# 5VV10_AND_BUCK.net
KiCad netlist of a schematic drawn in Altium Designer
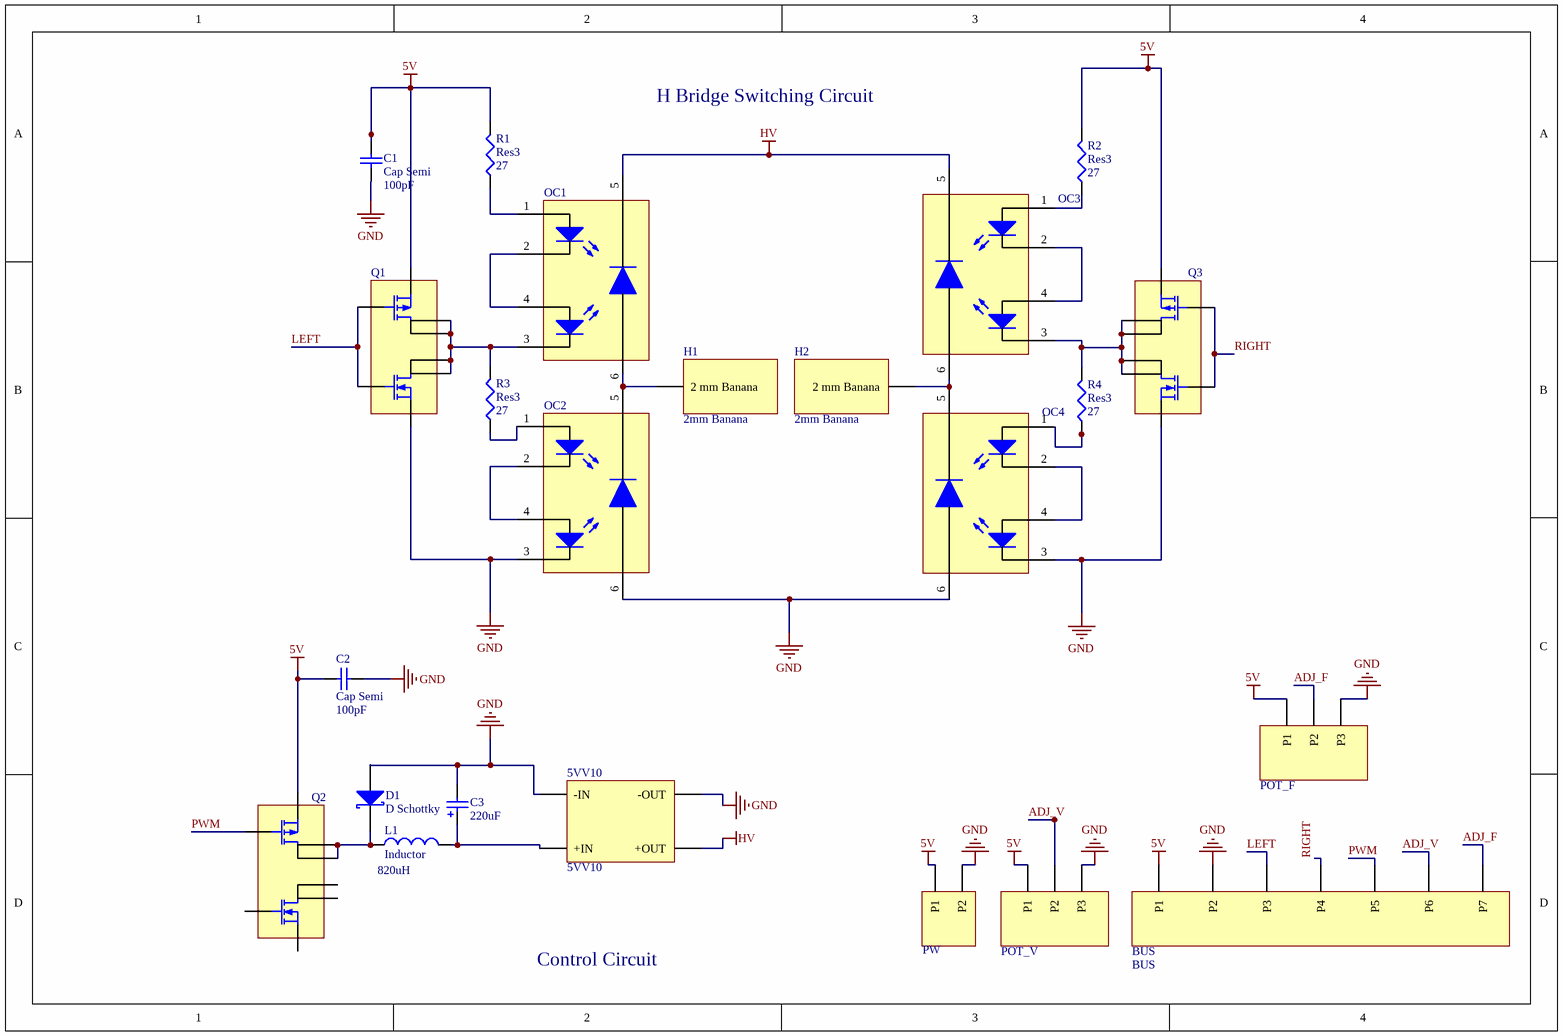
[diagram p0: 5VV10 AND BUCK.SchDoc]

(export (version "E")
  (design (tool "Eeschema 10.0.6"))
  (components
    (comp (ref "5VV10") (value "5VV10") (footprint "PCBComponent_1") (libsource (lib "5VV10") (part "5VV10")))
    (comp (ref "BUS")
      (value "BUS")
      (footprint "WJ350_7_Pins")
      (libsource (lib "WJ350_7_Pins") (part "WJ350_6_Pins"))
    )
    (comp (ref "C1")
      (value "Cap Semi")
      (footprint "C1206")
      (description "Capacitor (Semiconductor SIM Model)")
      (fields (field (name "ALTIUM_VALUE") "100pF") (field (name "PUBLISHER") "Altium Limited"))
      (libsource (lib "Miscellaneous Devices") (part "Cap Semi"))
    )
    (comp (ref "C2")
      (value "Cap Semi")
      (footprint "C1206")
      (description "Capacitor (Semiconductor SIM Model)")
      (fields (field (name "ALTIUM_VALUE") "100pF") (field (name "PUBLISHER") "Altium Limited"))
      (libsource (lib "Miscellaneous Devices") (part "Cap Semi"))
    )
    (comp (ref "C3")
      (value "220uF")
      (footprint "SMD 7343 - Pol")
      (description "Capacitor 220uF (Polarized)")
      (fields (field (name "PUBLISHER") "Altium Limited"))
      (libsource (lib "HV_COMPONENT") (part "Capacitor 220uF (Polarized)"))
    )
    (comp (ref "D1")
      (value "D Schottky")
      (footprint "SMB")
      (description "Schottky Diode")
      (fields (field (name "PUBLISHER") "Altium Limited"))
      (libsource (lib "Miscellaneous Devices") (part "D Schottky"))
    )
    (comp (ref "H1")
      (value "2mm Banana")
      (footprint "PCBComponent_1")
      (libsource (lib "2mm Banana") (part "2mm Banana"))
    )
    (comp (ref "H2")
      (value "2mm Banana")
      (footprint "PCBComponent_1")
      (libsource (lib "") (part "2mm Banana_1"))
    )
    (comp (ref "L1")
      (value "Inductor")
      (footprint "PCBComponent_1")
      (fields (field (name "ALTIUM_VALUE") "820uH"))
      (libsource (lib "820u Inductor") (part "820u"))
    )
    (comp (ref "OC1")
      (value "Optocoupler")
      (footprint "OC100G")
      (description "Manufacturer OC100G MPI distribution OC100G")
      (libsource (lib "Schlib") (part "Optocoupler"))
    )
    (comp (ref "OC2")
      (value "Optocoupler")
      (footprint "OC100G")
      (description "Manufacturer OC100G MPI distribution OC100G")
      (libsource (lib "Schlib") (part "Optocoupler"))
    )
    (comp (ref "OC3")
      (value "Optocoupler")
      (footprint "OC100G")
      (description "Manufacturer OC100G MPI distribution OC100G")
      (libsource (lib "") (part "Optocoupler_1"))
    )
    (comp (ref "OC4")
      (value "Optocoupler")
      (footprint "OC100G")
      (description "Manufacturer OC100G MPI distribution OC100G")
      (libsource (lib "") (part "Optocoupler_1"))
    )
    (comp (ref "POT_F")
      (value "POT")
      (footprint "WJ350_3_Pins")
      (libsource (lib "WJ350_3_Pins") (part "WJ350_3_Pins"))
    )
    (comp (ref "POT_V")
      (value "POT")
      (footprint "WJ350_3_Pins")
      (libsource (lib "WJ350_3_Pins") (part "WJ350_3_Pins"))
    )
    (comp (ref "PW")
      (value "PW")
      (footprint "WJ350_2_Pins")
      (libsource (lib "WJ350_2_Pins") (part "WJ350_2_Pins"))
    )
    (comp (ref "Q1")
      (value "Dual MOSFET")
      (footprint "SO-8")
      (description "Manufacturer FDS8858CZ Farnell 1498963")
      (libsource (lib "Schlib") (part "Dual MOSFET"))
    )
    (comp (ref "Q2")
      (value "Dual MOSFET")
      (footprint "SO-8")
      (description "Manufacturer FDS8858CZ Farnell 1498963")
      (libsource (lib "Schlib") (part "Dual MOSFET"))
    )
    (comp (ref "Q3")
      (value "Dual MOSFET")
      (footprint "SO-8")
      (description "Manufacturer FDS8858CZ Farnell 1498963")
      (libsource (lib "") (part "Dual MOSFET_1"))
    )
    (comp (ref "R1")
      (value "Res3")
      (footprint "14-1210")
      (description "Resistor")
      (fields (field (name "ALTIUM_VALUE") "27") (field (name "PUBLISHER") "Altium Limited"))
      (libsource (lib "Miscellaneous Devices") (part "Res3"))
    )
    (comp (ref "R2")
      (value "Res3")
      (footprint "14-1210")
      (description "Resistor")
      (fields (field (name "ALTIUM_VALUE") "27") (field (name "PUBLISHER") "Altium Limited"))
      (libsource (lib "Miscellaneous Devices") (part "Res3"))
    )
    (comp (ref "R3")
      (value "Res3")
      (footprint "14-1210")
      (description "Resistor")
      (fields (field (name "ALTIUM_VALUE") "27") (field (name "PUBLISHER") "Altium Limited"))
      (libsource (lib "Miscellaneous Devices") (part "Res3"))
    )
    (comp (ref "R4")
      (value "Res3")
      (footprint "14-1210")
      (description "Resistor")
      (fields (field (name "ALTIUM_VALUE") "27") (field (name "PUBLISHER") "Altium Limited"))
      (libsource (lib "Miscellaneous Devices") (part "Res3"))
    )
  )
  (nets
    (net (code "1") (name "/ADJ_F") (class "Default")
      (node (ref "BUS") (pin "P7") (pinfunction "P7_P7") (pintype "passive"))
      (node (ref "POT_F") (pin "P2") (pinfunction "P2_P2") (pintype "passive"))
    )
    (net (code "2") (name "/ADJ_V") (class "Default")
      (node (ref "BUS") (pin "P6") (pinfunction "P6_P6") (pintype "passive"))
      (node (ref "POT_V") (pin "P2") (pinfunction "P2_P2") (pintype "passive"))
    )
    (net (code "3") (name "/LEFT") (class "Default")
      (node (ref "BUS") (pin "P3") (pinfunction "P3_P3") (pintype "passive"))
      (node (ref "Q1") (pin "2") (pinfunction "2_2") (pintype "passive"))
      (node (ref "Q1") (pin "4") (pinfunction "4_4") (pintype "passive"))
    )
    (net (code "4") (name "/PWM") (class "Default")
      (node (ref "BUS") (pin "P5") (pinfunction "P5_P5") (pintype "passive"))
      (node (ref "Q2") (pin "4") (pinfunction "4_4") (pintype "passive"))
    )
    (net (code "5") (name "/RIGHT") (class "Default")
      (node (ref "BUS") (pin "P4") (pinfunction "P4_P4") (pintype "passive"))
      (node (ref "Q3") (pin "2") (pinfunction "2_2") (pintype "passive"))
      (node (ref "Q3") (pin "4") (pinfunction "4_4") (pintype "passive"))
    )
    (net (code "6") (name "5V") (class "Default")
      (node (ref "BUS") (pin "P1") (pinfunction "P1_P1") (pintype "passive"))
      (node (ref "C1") (pin "2") (pinfunction "2_2") (pintype "passive"))
      (node (ref "C2") (pin "1") (pinfunction "1_1") (pintype "passive"))
      (node (ref "POT_F") (pin "P1") (pinfunction "P1_P1") (pintype "passive"))
      (node (ref "POT_V") (pin "P1") (pinfunction "P1_P1") (pintype "passive"))
      (node (ref "PW") (pin "P1") (pinfunction "P1_P1") (pintype "passive"))
      (node (ref "Q1") (pin "3") (pinfunction "3_3") (pintype "passive"))
      (node (ref "Q2") (pin "3") (pinfunction "3_3") (pintype "passive"))
      (node (ref "Q3") (pin "3") (pinfunction "3_3") (pintype "passive"))
      (node (ref "R1") (pin "2") (pinfunction "2_2") (pintype "passive"))
      (node (ref "R2") (pin "2") (pinfunction "2_2") (pintype "passive"))
    )
    (net (code "7") (name "GND") (class "Default")
      (node (ref "5VV10") (pin "1") (pinfunction "-IN_1") (pintype "passive"))
      (node (ref "5VV10") (pin "4") (pinfunction "-OUT_4") (pintype "passive"))
      (node (ref "BUS") (pin "P2") (pinfunction "P2_P2") (pintype "passive"))
      (node (ref "C1") (pin "1") (pinfunction "1_1") (pintype "passive"))
      (node (ref "C2") (pin "2") (pinfunction "2_2") (pintype "passive"))
      (node (ref "C3") (pin "2") (pinfunction "2_2") (pintype "passive"))
      (node (ref "D1") (pin "1") (pinfunction "A_1") (pintype "passive"))
      (node (ref "OC2") (pin "3") (pinfunction "K_3") (pintype "passive"))
      (node (ref "OC2") (pin "6") (pinfunction "A_6") (pintype "passive"))
      (node (ref "OC4") (pin "3") (pinfunction "K_3") (pintype "passive"))
      (node (ref "OC4") (pin "6") (pinfunction "A_6") (pintype "passive"))
      (node (ref "POT_F") (pin "P3") (pinfunction "P3_P3") (pintype "passive"))
      (node (ref "POT_V") (pin "P3") (pinfunction "P3_P3") (pintype "passive"))
      (node (ref "PW") (pin "P2") (pinfunction "P2_P2") (pintype "passive"))
      (node (ref "Q1") (pin "1") (pinfunction "1_1") (pintype "passive"))
      (node (ref "Q3") (pin "1") (pinfunction "1_1") (pintype "passive"))
    )
    (net (code "8") (name "HV") (class "Default")
      (node (ref "5VV10") (pin "3") (pinfunction "+OUT_3") (pintype "passive"))
      (node (ref "OC1") (pin "5") (pinfunction "K_5") (pintype "passive"))
      (node (ref "OC3") (pin "5") (pinfunction "K_5") (pintype "passive"))
    )
    (net (code "9") (name "Net-(5VV10-+IN)") (class "Default")
      (node (ref "5VV10") (pin "2") (pinfunction "+IN_2") (pintype "passive"))
      (node (ref "C3") (pin "1") (pinfunction "1_1") (pintype "passive"))
      (node (ref "L1") (pin "2") (pinfunction "2_2") (pintype "passive"))
    )
    (net (code "10") (name "Net-(D1-K)") (class "Default")
      (node (ref "D1") (pin "2") (pinfunction "K_2") (pintype "passive"))
      (node (ref "L1") (pin "1") (pinfunction "1_1") (pintype "passive"))
      (node (ref "Q2") (pin "5") (pinfunction "5_5") (pintype "passive"))
      (node (ref "Q2") (pin "6") (pinfunction "6_6") (pintype "passive"))
    )
    (net (code "11") (name "Net-(H1-2_mm_Banana)") (class "Default")
      (node (ref "H1") (pin "1") (pinfunction "2_mm_Banana_1") (pintype "passive"))
      (node (ref "OC1") (pin "6") (pinfunction "A_6") (pintype "passive"))
      (node (ref "OC2") (pin "5") (pinfunction "K_5") (pintype "passive"))
    )
    (net (code "12") (name "Net-(H2-2_mm_Banana)") (class "Default")
      (node (ref "H2") (pin "1") (pinfunction "2_mm_Banana_1") (pintype "passive"))
      (node (ref "OC3") (pin "6") (pinfunction "A_6") (pintype "passive"))
      (node (ref "OC4") (pin "5") (pinfunction "K_5") (pintype "passive"))
    )
    (net (code "13") (name "Net-(OC1-A-Pad1)") (class "Default")
      (node (ref "OC1") (pin "1") (pinfunction "A_1") (pintype "passive"))
      (node (ref "R1") (pin "1") (pinfunction "1_1") (pintype "passive"))
    )
    (net (code "14") (name "Net-(OC1-A-Pad4)") (class "Default")
      (node (ref "OC1") (pin "2") (pinfunction "K_2") (pintype "passive"))
      (node (ref "OC1") (pin "4") (pinfunction "A_4") (pintype "passive"))
    )
    (net (code "15") (name "Net-(OC1-K-Pad3)") (class "Default")
      (node (ref "OC1") (pin "3") (pinfunction "K_3") (pintype "passive"))
      (node (ref "Q1") (pin "5") (pinfunction "5_5") (pintype "passive"))
      (node (ref "Q1") (pin "6") (pinfunction "6_6") (pintype "passive"))
      (node (ref "Q1") (pin "7") (pinfunction "7_7") (pintype "passive"))
      (node (ref "Q1") (pin "8") (pinfunction "8_8") (pintype "passive"))
      (node (ref "R3") (pin "2") (pinfunction "2_2") (pintype "passive"))
    )
    (net (code "16") (name "Net-(OC2-A-Pad1)") (class "Default")
      (node (ref "OC2") (pin "1") (pinfunction "A_1") (pintype "passive"))
      (node (ref "R3") (pin "1") (pinfunction "1_1") (pintype "passive"))
    )
    (net (code "17") (name "Net-(OC2-A-Pad4)") (class "Default")
      (node (ref "OC2") (pin "2") (pinfunction "K_2") (pintype "passive"))
      (node (ref "OC2") (pin "4") (pinfunction "A_4") (pintype "passive"))
    )
    (net (code "18") (name "Net-(OC3-A-Pad1)") (class "Default")
      (node (ref "OC3") (pin "1") (pinfunction "A_1") (pintype "passive"))
      (node (ref "R2") (pin "1") (pinfunction "1_1") (pintype "passive"))
    )
    (net (code "19") (name "Net-(OC3-A-Pad4)") (class "Default")
      (node (ref "OC3") (pin "2") (pinfunction "K_2") (pintype "passive"))
      (node (ref "OC3") (pin "4") (pinfunction "A_4") (pintype "passive"))
    )
    (net (code "20") (name "Net-(OC3-K-Pad3)") (class "Default")
      (node (ref "OC3") (pin "3") (pinfunction "K_3") (pintype "passive"))
      (node (ref "Q3") (pin "5") (pinfunction "5_5") (pintype "passive"))
      (node (ref "Q3") (pin "6") (pinfunction "6_6") (pintype "passive"))
      (node (ref "Q3") (pin "7") (pinfunction "7_7") (pintype "passive"))
      (node (ref "Q3") (pin "8") (pinfunction "8_8") (pintype "passive"))
      (node (ref "R4") (pin "2") (pinfunction "2_2") (pintype "passive"))
    )
    (net (code "21") (name "Net-(OC4-A-Pad1)") (class "Default")
      (node (ref "OC4") (pin "1") (pinfunction "A_1") (pintype "passive"))
      (node (ref "R4") (pin "1") (pinfunction "1_1") (pintype "passive"))
    )
    (net (code "22") (name "Net-(OC4-A-Pad4)") (class "Default")
      (node (ref "OC4") (pin "2") (pinfunction "K_2") (pintype "passive"))
      (node (ref "OC4") (pin "4") (pinfunction "A_4") (pintype "passive"))
    )
    (net (code "23") (name "unconnected-(Q2-Pad1)") (class "Default")
      (node (ref "Q2") (pin "1") (pinfunction "1_1") (pintype "passive"))
    )
    (net (code "24") (name "unconnected-(Q2-Pad2)") (class "Default")
      (node (ref "Q2") (pin "2") (pinfunction "2_2") (pintype "passive"))
    )
    (net (code "25") (name "unconnected-(Q2-Pad7)") (class "Default")
      (node (ref "Q2") (pin "7") (pinfunction "7_7") (pintype "passive"))
    )
    (net (code "26") (name "unconnected-(Q2-Pad8)") (class "Default")
      (node (ref "Q2") (pin "8") (pinfunction "8_8") (pintype "passive"))
    )
  )
)
